# LPEM.net
KiCad netlist of a schematic drawn in EAGLE
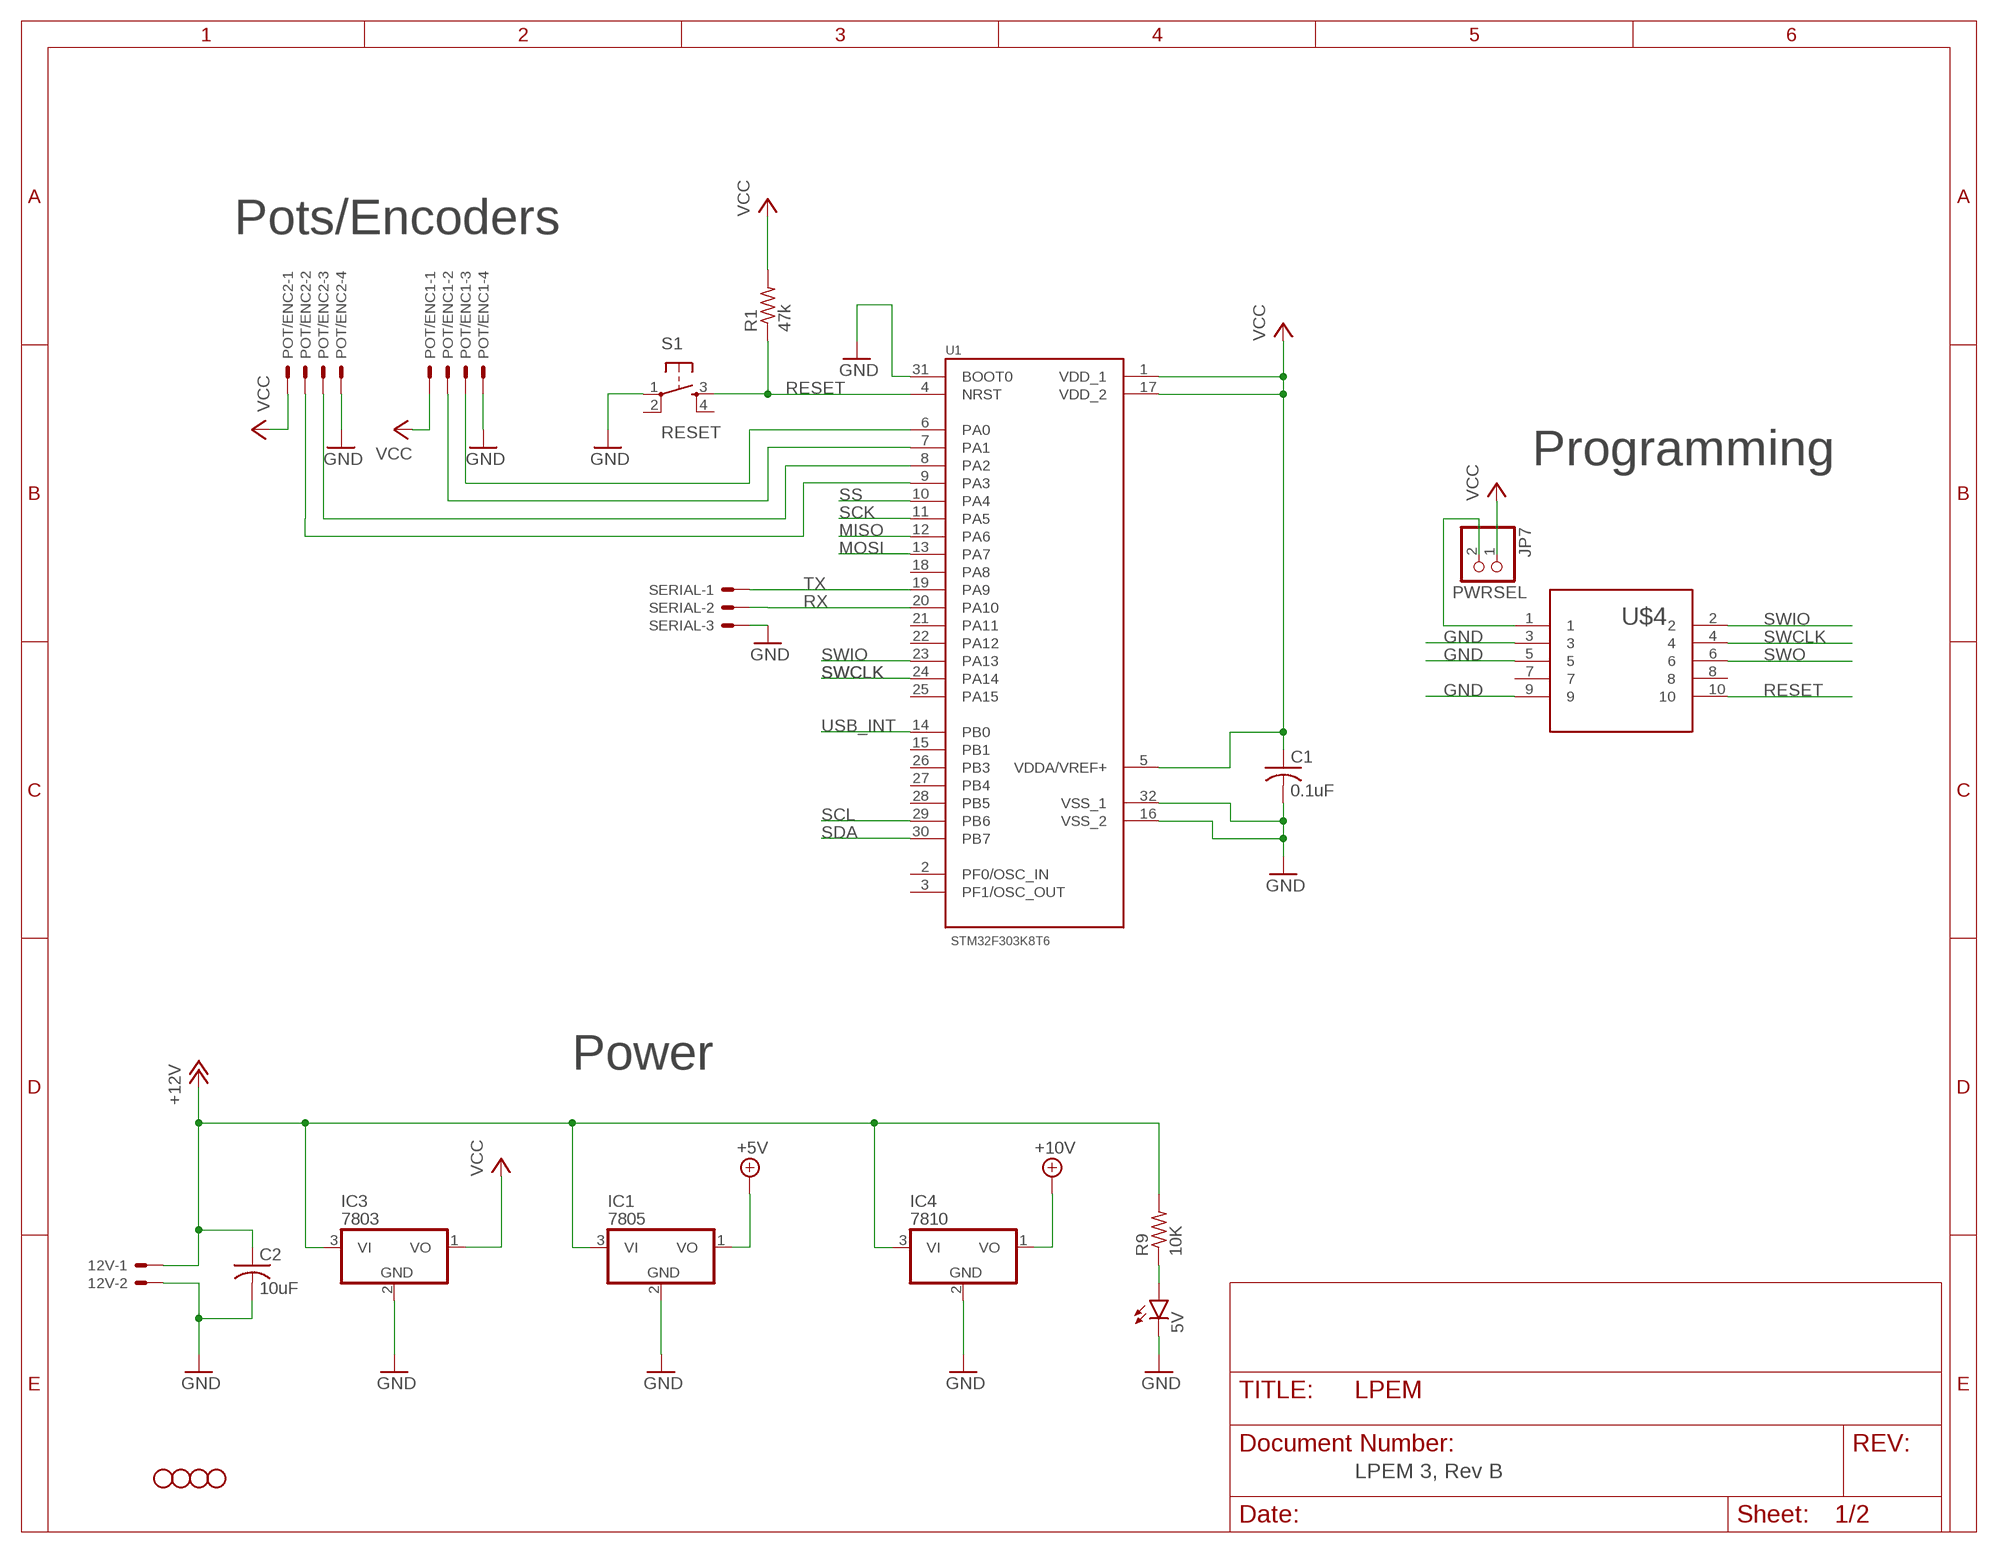
[diagram p0: schematic, sheet 1]
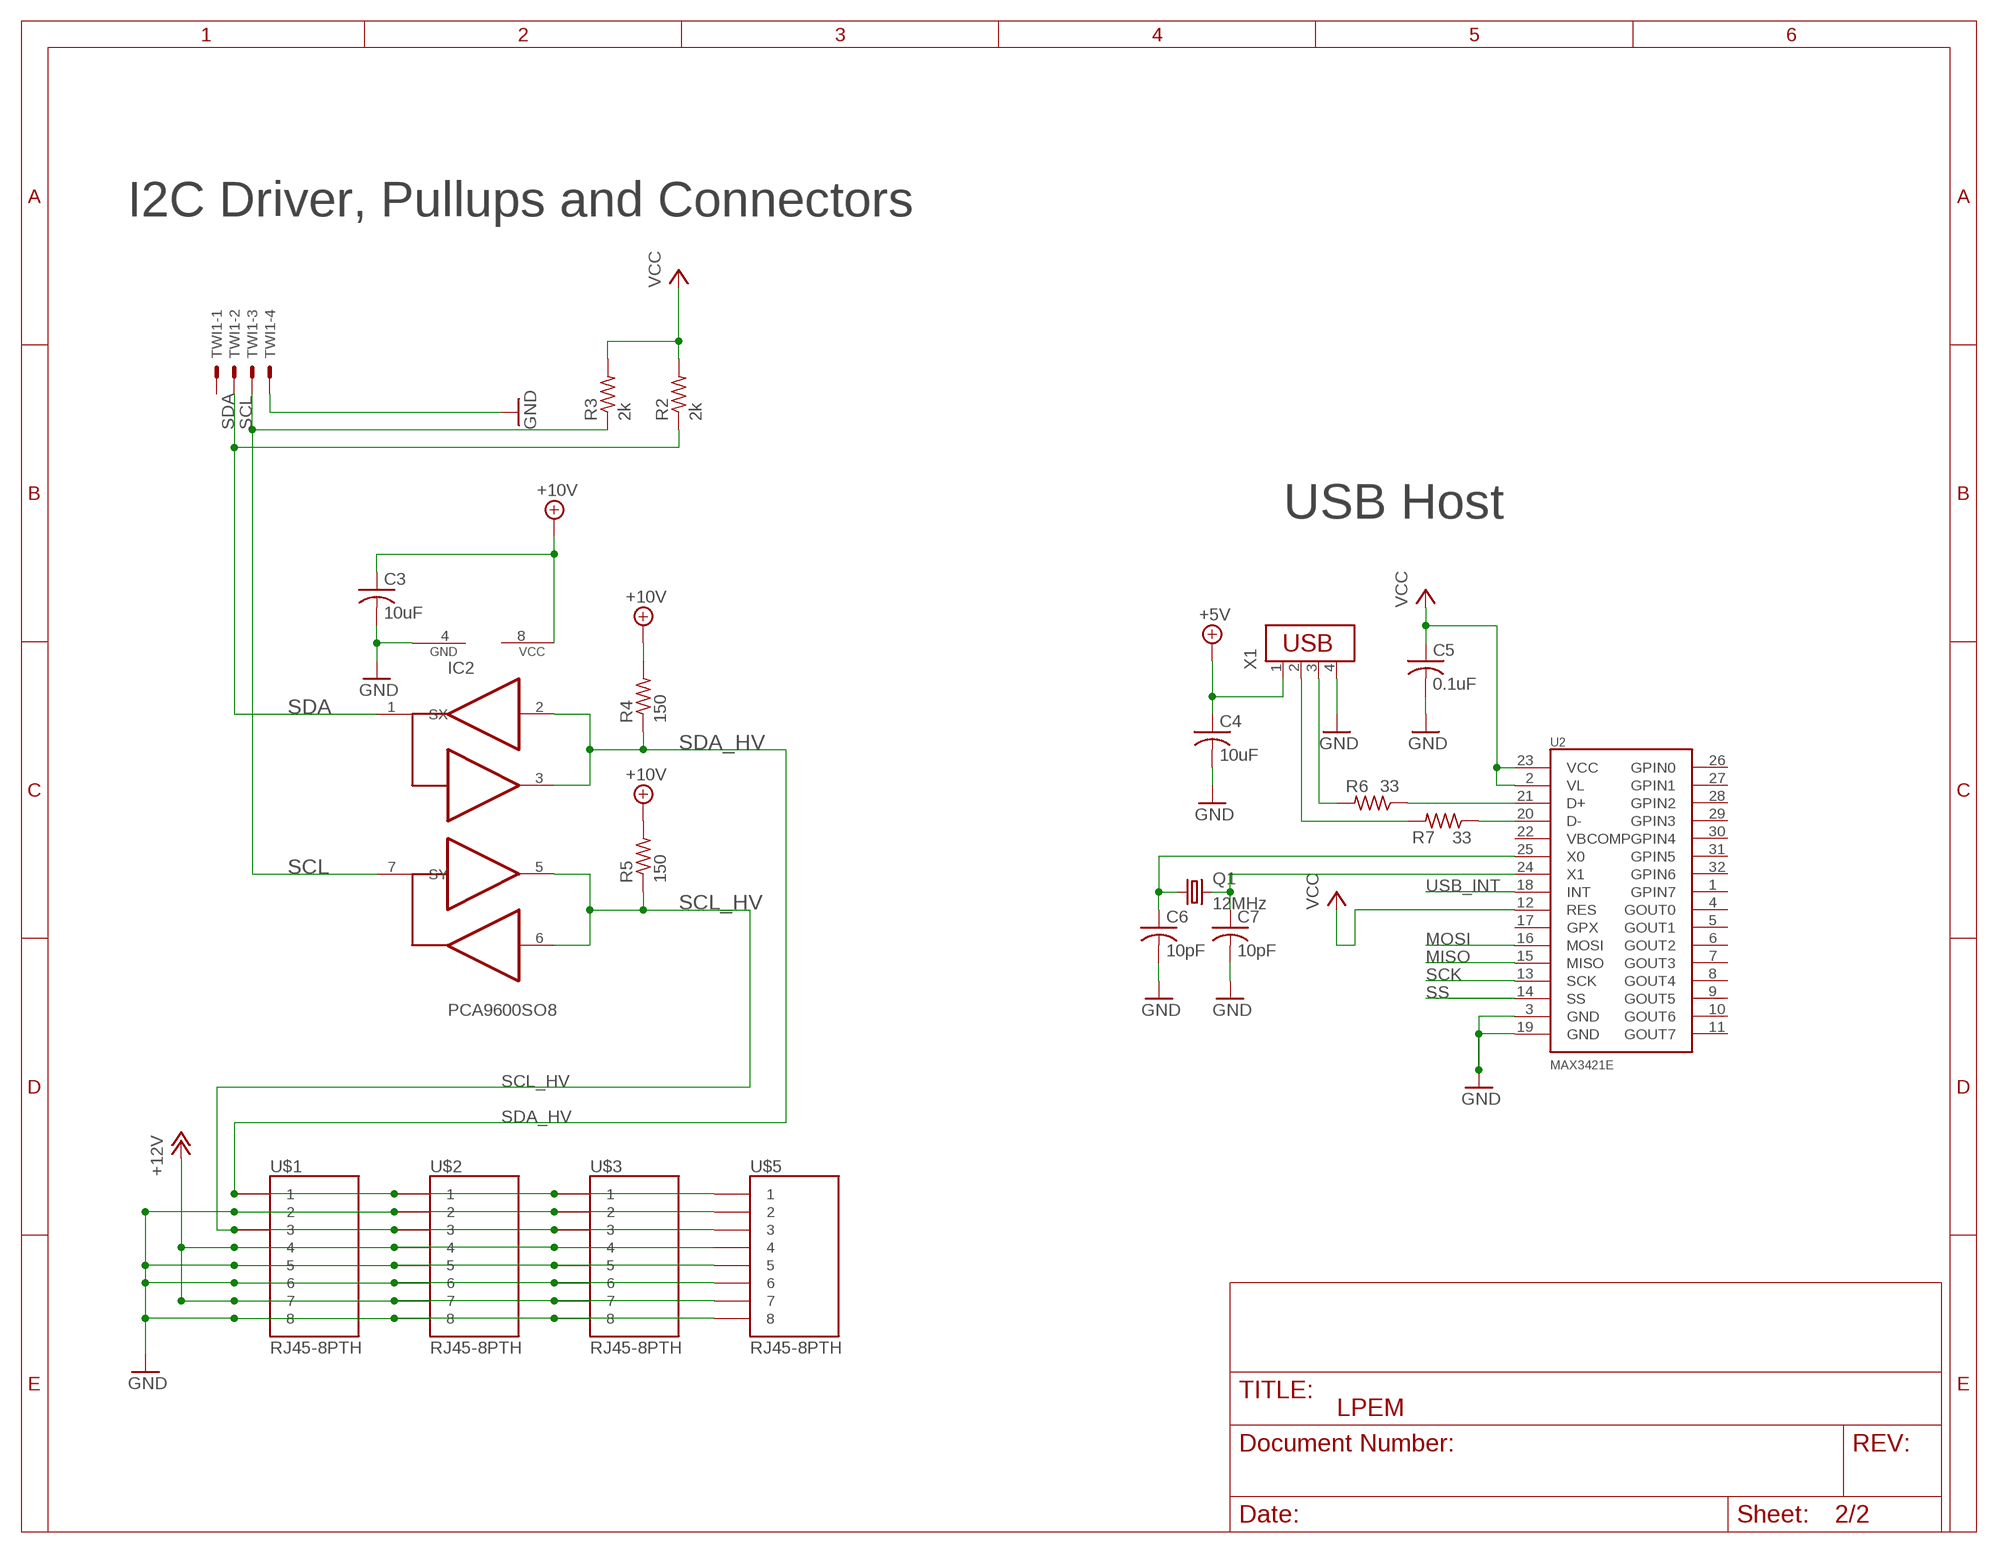
[diagram p1: schematic, sheet 2]

(export (version "E")
  (design (tool "Eeschema 10.0.6"))
  (components
    (comp (ref "C3")
      (value "10uF")
      (footprint "eagle-import:C025-025X050")
      (libsource (lib "eagle-import") (part "C-US025-025X050"))
    )
    (comp (ref "C4")
      (value "10uF")
      (footprint "eagle-import:C025-025X050")
      (libsource (lib "eagle-import") (part "C-US025-025X050"))
    )
    (comp (ref "C5")
      (value "0.1uF")
      (footprint "eagle-import:C025-025X050")
      (libsource (lib "eagle-import") (part "C-US025-025X050"))
    )
    (comp (ref "C6")
      (value "10pF")
      (footprint "eagle-import:C025-025X050")
      (libsource (lib "eagle-import") (part "C-US025-025X050"))
    )
    (comp (ref "C7")
      (value "10pF")
      (footprint "eagle-import:C025-025X050")
      (libsource (lib "eagle-import") (part "C-US025-025X050"))
    )
    (comp (ref "IC2")
      (value "PCA9600SO8")
      (footprint "eagle-import:SO08")
      (libsource (lib "eagle-import") (part "PCA9600SO8"))
    )
    (comp (ref "Q1")
      (value "12MHz")
      (footprint "eagle-import:HC18U-V")
      (libsource (lib "eagle-import") (part "CRYSTALHC18U-V"))
    )
    (comp (ref "R2")
      (value "2k")
      (footprint "eagle-import:0204_5")
      (libsource (lib "eagle-import") (part "R-US_0204/5"))
    )
    (comp (ref "R3")
      (value "2k")
      (footprint "eagle-import:0204_5")
      (libsource (lib "eagle-import") (part "R-US_0204/5"))
    )
    (comp (ref "R4")
      (value "150")
      (footprint "eagle-import:0204_5")
      (libsource (lib "eagle-import") (part "R-US_0204/5"))
    )
    (comp (ref "R5")
      (value "150")
      (footprint "eagle-import:0204_5")
      (libsource (lib "eagle-import") (part "R-US_0204/5"))
    )
    (comp (ref "R6")
      (value "33")
      (footprint "eagle-import:0204_5")
      (libsource (lib "eagle-import") (part "R-US_0204/5"))
    )
    (comp (ref "R7")
      (value "33")
      (footprint "eagle-import:0204_5")
      (libsource (lib "eagle-import") (part "R-US_0204/5"))
    )
    (comp (ref "TWI1")
      (value "22-23-2041")
      (footprint "eagle-import:22-23-2041")
      (fields (field (name "MF") "MOLEX"))
      (libsource (lib "eagle-import") (part "22-23-2041"))
    )
    (comp (ref "U$1")
      (value "RJ45-8PTH")
      (footprint "eagle-import:RJ45-8")
      (libsource (lib "eagle-import") (part "RJ45-8PTH"))
    )
    (comp (ref "U$2")
      (value "RJ45-8PTH")
      (footprint "eagle-import:RJ45-8")
      (libsource (lib "eagle-import") (part "RJ45-8PTH"))
    )
    (comp (ref "U$3")
      (value "RJ45-8PTH")
      (footprint "eagle-import:RJ45-8")
      (libsource (lib "eagle-import") (part "RJ45-8PTH"))
    )
    (comp (ref "U$5")
      (value "RJ45-8PTH")
      (footprint "eagle-import:RJ45-8")
      (libsource (lib "eagle-import") (part "RJ45-8PTH"))
    )
    (comp (ref "U2")
      (value "MAX3421E")
      (footprint "eagle-import:TQFP32-5MM")
      (fields (field (name "MF") "Maxim Integrated"))
      (libsource (lib "eagle-import") (part "MAX3421E"))
    )
    (comp (ref "X1")
      (value "USB-787616")
      (footprint "eagle-import:USB")
      (libsource (lib "eagle-import") (part "USB-787616"))
    )
    (comp (ref "5V")
      (value "LED3MM")
      (footprint "eagle-import:LED3MM")
      (libsource (lib "eagle-import") (part "LED3MM"))
    )
    (comp (ref "12V")
      (value "22-23-2021")
      (footprint "eagle-import:22-23-2021")
      (fields (field (name "MF") "MOLEX"))
      (libsource (lib "eagle-import") (part "22-23-2021"))
    )
    (comp (ref "C1")
      (value "0.1uF")
      (footprint "eagle-import:C025-025X050")
      (libsource (lib "eagle-import") (part "C-US025-025X050"))
    )
    (comp (ref "C2")
      (value "10uF")
      (footprint "eagle-import:C025-025X050")
      (libsource (lib "eagle-import") (part "C-US025-025X050"))
    )
    (comp (ref "IC1")
      (value "7805")
      (footprint "eagle-import:TO92")
      (libsource (lib "eagle-import") (part "78ZL05"))
    )
    (comp (ref "IC3")
      (value "7803")
      (footprint "eagle-import:TO92")
      (libsource (lib "eagle-import") (part "78ZL05"))
    )
    (comp (ref "IC4")
      (value "7810")
      (footprint "eagle-import:TO92")
      (libsource (lib "eagle-import") (part "78ZL05"))
    )
    (comp (ref "JP1")
      (value "STAND-OFF")
      (footprint "eagle-import:STAND-OFF")
      (libsource (lib "eagle-import") (part "STAND-OFF"))
    )
    (comp (ref "JP2")
      (value "STAND-OFF")
      (footprint "eagle-import:STAND-OFF")
      (libsource (lib "eagle-import") (part "STAND-OFF"))
    )
    (comp (ref "JP7")
      (value "PWRSEL")
      (footprint "eagle-import:1X02")
      (libsource (lib "eagle-import") (part "PINHD-1X2"))
    )
    (comp (ref "JP8")
      (value "STAND-OFF")
      (footprint "eagle-import:STAND-OFF")
      (libsource (lib "eagle-import") (part "STAND-OFF"))
    )
    (comp (ref "JP9")
      (value "STAND-OFF")
      (footprint "eagle-import:STAND-OFF")
      (libsource (lib "eagle-import") (part "STAND-OFF"))
    )
    (comp (ref "POT/ENC1")
      (value "22-23-2041")
      (footprint "eagle-import:22-23-2041")
      (fields (field (name "MF") "MOLEX"))
      (libsource (lib "eagle-import") (part "22-23-2041"))
    )
    (comp (ref "POT/ENC2")
      (value "22-23-2041")
      (footprint "eagle-import:22-23-2041")
      (fields (field (name "MF") "MOLEX"))
      (libsource (lib "eagle-import") (part "22-23-2041"))
    )
    (comp (ref "R1")
      (value "47k")
      (footprint "eagle-import:0204_5")
      (libsource (lib "eagle-import") (part "R-US_0204/5"))
    )
    (comp (ref "R9")
      (value "10K")
      (footprint "eagle-import:0204_5")
      (libsource (lib "eagle-import") (part "R-US_0204/5"))
    )
    (comp (ref "S1")
      (value "RESET")
      (footprint "eagle-import:TACTILE-PTH")
      (libsource (lib "eagle-import") (part "TAC_SWITCHPTH"))
    )
    (comp (ref "SERIAL")
      (value "22-23-2031")
      (footprint "eagle-import:22-23-2031")
      (fields (field (name "MF") "MOLEX"))
      (libsource (lib "eagle-import") (part "22-23-2031"))
    )
    (comp (ref "U$4")
      (value "CORTEX_HEADERJ")
      (footprint "eagle-import:CORTEX_HEADER")
      (fields (field (name "MF") "Samtec Inc.") (field (name "MP") "TFM-105-01-S-D-WT"))
      (libsource (lib "eagle-import") (part "CORTEX_HEADERJ"))
    )
    (comp (ref "U1")
      (value "STM32F303K8T6")
      (footprint "eagle-import:QFP80P900X900X160-32N")
      (fields (field (name "MF") "STMicroelectronics"))
      (libsource (lib "eagle-import") (part "STM32F303K8T6"))
    )
  )
  (nets
    (net (code "1") (name "+5V") (class "Default")
      (node (ref "C4") (pin "1") (pinfunction "1_1") (pintype "passive"))
      (node (ref "IC1") (pin "1") (pinfunction "VO_1") (pintype "passive"))
      (node (ref "X1") (pin "1") (pinfunction "1_1") (pintype "passive"))
    )
    (net (code "2") (name "+10V") (class "Default")
      (node (ref "C3") (pin "1") (pinfunction "1_1") (pintype "passive"))
      (node (ref "IC2") (pin "8") (pinfunction "VCC_8") (pintype "power_in"))
      (node (ref "IC4") (pin "1") (pinfunction "VO_1") (pintype "passive"))
      (node (ref "R4") (pin "2") (pinfunction "2_2") (pintype "passive"))
      (node (ref "R5") (pin "2") (pinfunction "2_2") (pintype "passive"))
    )
    (net (code "3") (name "+12V") (class "Default")
      (node (ref "12V") (pin "1") (pinfunction "S_1") (pintype "passive"))
      (node (ref "C2") (pin "1") (pinfunction "1_1") (pintype "passive"))
      (node (ref "IC1") (pin "3") (pinfunction "VI_3") (pintype "input"))
      (node (ref "IC3") (pin "3") (pinfunction "VI_3") (pintype "input"))
      (node (ref "IC4") (pin "3") (pinfunction "VI_3") (pintype "input"))
      (node (ref "R9") (pin "2") (pinfunction "2_2") (pintype "passive"))
      (node (ref "U$1") (pin "4") (pinfunction "4_4") (pintype "bidirectional"))
      (node (ref "U$1") (pin "7") (pinfunction "7_7") (pintype "bidirectional"))
      (node (ref "U$2") (pin "4") (pinfunction "4_4") (pintype "bidirectional"))
      (node (ref "U$2") (pin "7") (pinfunction "7_7") (pintype "bidirectional"))
      (node (ref "U$3") (pin "4") (pinfunction "4_4") (pintype "bidirectional"))
      (node (ref "U$3") (pin "7") (pinfunction "7_7") (pintype "bidirectional"))
      (node (ref "U$5") (pin "4") (pinfunction "4_4") (pintype "bidirectional"))
      (node (ref "U$5") (pin "7") (pinfunction "7_7") (pintype "bidirectional"))
    )
    (net (code "4") (name "GND") (class "Default")
      (node (ref "12V") (pin "2") (pinfunction "S_2") (pintype "passive"))
      (node (ref "5V") (pin "K") (pinfunction "C_K") (pintype "passive"))
      (node (ref "C1") (pin "2") (pinfunction "2_2") (pintype "passive"))
      (node (ref "C2") (pin "2") (pinfunction "2_2") (pintype "passive"))
      (node (ref "C3") (pin "2") (pinfunction "2_2") (pintype "passive"))
      (node (ref "C4") (pin "2") (pinfunction "2_2") (pintype "passive"))
      (node (ref "C5") (pin "2") (pinfunction "2_2") (pintype "passive"))
      (node (ref "C6") (pin "2") (pinfunction "2_2") (pintype "passive"))
      (node (ref "C7") (pin "2") (pinfunction "2_2") (pintype "passive"))
      (node (ref "IC1") (pin "2") (pinfunction "GND_2") (pintype "passive"))
      (node (ref "IC2") (pin "4") (pinfunction "GND_4") (pintype "power_in"))
      (node (ref "IC3") (pin "2") (pinfunction "GND_2") (pintype "passive"))
      (node (ref "IC4") (pin "2") (pinfunction "GND_2") (pintype "passive"))
      (node (ref "POT/ENC1") (pin "4") (pinfunction "S_4") (pintype "passive"))
      (node (ref "POT/ENC2") (pin "4") (pinfunction "S_4") (pintype "passive"))
      (node (ref "S1") (pin "1") (pinfunction "1_1") (pintype "passive"))
      (node (ref "SERIAL") (pin "3") (pinfunction "S_3") (pintype "passive"))
      (node (ref "TWI1") (pin "4") (pinfunction "S_4") (pintype "passive"))
      (node (ref "U$1") (pin "2") (pinfunction "2_2") (pintype "bidirectional"))
      (node (ref "U$1") (pin "5") (pinfunction "5_5") (pintype "bidirectional"))
      (node (ref "U$1") (pin "6") (pinfunction "6_6") (pintype "bidirectional"))
      (node (ref "U$1") (pin "8") (pinfunction "8_8") (pintype "bidirectional"))
      (node (ref "U$2") (pin "2") (pinfunction "2_2") (pintype "bidirectional"))
      (node (ref "U$2") (pin "5") (pinfunction "5_5") (pintype "bidirectional"))
      (node (ref "U$2") (pin "6") (pinfunction "6_6") (pintype "bidirectional"))
      (node (ref "U$2") (pin "8") (pinfunction "8_8") (pintype "bidirectional"))
      (node (ref "U$3") (pin "2") (pinfunction "2_2") (pintype "bidirectional"))
      (node (ref "U$3") (pin "5") (pinfunction "5_5") (pintype "bidirectional"))
      (node (ref "U$3") (pin "6") (pinfunction "6_6") (pintype "bidirectional"))
      (node (ref "U$3") (pin "8") (pinfunction "8_8") (pintype "bidirectional"))
      (node (ref "U$4") (pin "3") (pinfunction "3_3") (pintype "passive"))
      (node (ref "U$4") (pin "5") (pinfunction "5_5") (pintype "passive"))
      (node (ref "U$4") (pin "9") (pinfunction "9_9") (pintype "passive"))
      (node (ref "U$5") (pin "2") (pinfunction "2_2") (pintype "bidirectional"))
      (node (ref "U$5") (pin "5") (pinfunction "5_5") (pintype "bidirectional"))
      (node (ref "U$5") (pin "6") (pinfunction "6_6") (pintype "bidirectional"))
      (node (ref "U$5") (pin "8") (pinfunction "8_8") (pintype "bidirectional"))
      (node (ref "U1") (pin "16") (pinfunction "VSS_2_16") (pintype "power_in"))
      (node (ref "U1") (pin "31") (pinfunction "BOOT0_31") (pintype "input"))
      (node (ref "U1") (pin "32") (pinfunction "VSS_1_32") (pintype "power_in"))
      (node (ref "U2") (pin "19") (pinfunction "GND_19") (pintype "bidirectional"))
      (node (ref "U2") (pin "3") (pinfunction "GND_3") (pintype "bidirectional"))
      (node (ref "X1") (pin "4") (pinfunction "4_4") (pintype "passive"))
    )
    (net (code "5") (name "MISO") (class "Default")
      (node (ref "U1") (pin "12") (pinfunction "PA6_12") (pintype "bidirectional"))
      (node (ref "U2") (pin "15") (pinfunction "MISO_15") (pintype "bidirectional"))
    )
    (net (code "6") (name "MOSI") (class "Default")
      (node (ref "U1") (pin "13") (pinfunction "PA7_13") (pintype "bidirectional"))
      (node (ref "U2") (pin "16") (pinfunction "MOSI_16") (pintype "bidirectional"))
    )
    (net (code "7") (name "Net-(5V-PadA)") (class "Default")
      (node (ref "5V") (pin "A") (pinfunction "A_A") (pintype "passive"))
      (node (ref "R9") (pin "1") (pinfunction "1_1") (pintype "passive"))
    )
    (net (code "8") (name "Net-(JP7-Pad2)") (class "Default")
      (node (ref "JP7") (pin "2") (pinfunction "2_2") (pintype "passive"))
      (node (ref "U$4") (pin "1") (pinfunction "1_1") (pintype "passive"))
    )
    (net (code "9") (name "Net-(POT/ENC1B-S)") (class "Default")
      (node (ref "POT/ENC1") (pin "2") (pinfunction "S_2") (pintype "passive"))
      (node (ref "U1") (pin "7") (pinfunction "PA1_7") (pintype "bidirectional"))
    )
    (net (code "10") (name "Net-(POT/ENC1C-S)") (class "Default")
      (node (ref "POT/ENC1") (pin "3") (pinfunction "S_3") (pintype "passive"))
      (node (ref "U1") (pin "6") (pinfunction "PA0_6") (pintype "bidirectional"))
    )
    (net (code "11") (name "Net-(POT/ENC2B-S)") (class "Default")
      (node (ref "POT/ENC2") (pin "2") (pinfunction "S_2") (pintype "passive"))
      (node (ref "U1") (pin "9") (pinfunction "PA3_9") (pintype "bidirectional"))
    )
    (net (code "12") (name "Net-(POT/ENC2C-S)") (class "Default")
      (node (ref "POT/ENC2") (pin "3") (pinfunction "S_3") (pintype "passive"))
      (node (ref "U1") (pin "8") (pinfunction "PA2_8") (pintype "bidirectional"))
    )
    (net (code "13") (name "Net-(R6-Pad2)") (class "Default")
      (node (ref "R6") (pin "2") (pinfunction "2_2") (pintype "passive"))
      (node (ref "X1") (pin "3") (pinfunction "3_3") (pintype "passive"))
    )
    (net (code "14") (name "Net-(R7-Pad2)") (class "Default")
      (node (ref "R7") (pin "2") (pinfunction "2_2") (pintype "passive"))
      (node (ref "X1") (pin "2") (pinfunction "2_2") (pintype "passive"))
    )
    (net (code "15") (name "Net-(U2-D+)") (class "Default")
      (node (ref "R6") (pin "1") (pinfunction "1_1") (pintype "passive"))
      (node (ref "U2") (pin "21") (pinfunction "D+_21") (pintype "bidirectional"))
    )
    (net (code "16") (name "Net-(U2-D-)") (class "Default")
      (node (ref "R7") (pin "1") (pinfunction "1_1") (pintype "passive"))
      (node (ref "U2") (pin "20") (pinfunction "D-_20") (pintype "bidirectional"))
    )
    (net (code "17") (name "Net-(U2-X0)") (class "Default")
      (node (ref "C6") (pin "1") (pinfunction "1_1") (pintype "passive"))
      (node (ref "Q1") (pin "1") (pinfunction "1_1") (pintype "passive"))
      (node (ref "U2") (pin "25") (pinfunction "X0_25") (pintype "bidirectional"))
    )
    (net (code "18") (name "Net-(U2-X1)") (class "Default")
      (node (ref "C7") (pin "1") (pinfunction "1_1") (pintype "passive"))
      (node (ref "Q1") (pin "2") (pinfunction "2_2") (pintype "passive"))
      (node (ref "U2") (pin "24") (pinfunction "X1_24") (pintype "bidirectional"))
    )
    (net (code "19") (name "RESET") (class "Default")
      (node (ref "R1") (pin "1") (pinfunction "1_1") (pintype "passive"))
      (node (ref "S1") (pin "3") (pinfunction "3_3") (pintype "passive"))
      (node (ref "U$4") (pin "10") (pinfunction "10_10") (pintype "passive"))
      (node (ref "U1") (pin "4") (pinfunction "NRST_4") (pintype "bidirectional"))
    )
    (net (code "20") (name "RX") (class "Default")
      (node (ref "SERIAL") (pin "2") (pinfunction "S_2") (pintype "passive"))
      (node (ref "U1") (pin "20") (pinfunction "PA10_20") (pintype "bidirectional"))
    )
    (net (code "21") (name "SCK") (class "Default")
      (node (ref "U1") (pin "11") (pinfunction "PA5_11") (pintype "bidirectional"))
      (node (ref "U2") (pin "13") (pinfunction "SCK_13") (pintype "bidirectional"))
    )
    (net (code "22") (name "SCL") (class "Default")
      (node (ref "IC2") (pin "7") (pinfunction "SY_7") (pintype "bidirectional"))
      (node (ref "R3") (pin "1") (pinfunction "1_1") (pintype "passive"))
      (node (ref "TWI1") (pin "3") (pinfunction "S_3") (pintype "passive"))
      (node (ref "U1") (pin "29") (pinfunction "PB6_29") (pintype "bidirectional"))
    )
    (net (code "23") (name "SCL_HV") (class "Default")
      (node (ref "IC2") (pin "5") (pinfunction "TY_5") (pintype "output"))
      (node (ref "IC2") (pin "6") (pinfunction "RY_6") (pintype "input"))
      (node (ref "R5") (pin "1") (pinfunction "1_1") (pintype "passive"))
      (node (ref "U$1") (pin "3") (pinfunction "3_3") (pintype "bidirectional"))
      (node (ref "U$2") (pin "3") (pinfunction "3_3") (pintype "bidirectional"))
      (node (ref "U$3") (pin "3") (pinfunction "3_3") (pintype "bidirectional"))
      (node (ref "U$5") (pin "3") (pinfunction "3_3") (pintype "bidirectional"))
    )
    (net (code "24") (name "SDA") (class "Default")
      (node (ref "IC2") (pin "1") (pinfunction "SX_1") (pintype "bidirectional"))
      (node (ref "R2") (pin "1") (pinfunction "1_1") (pintype "passive"))
      (node (ref "TWI1") (pin "2") (pinfunction "S_2") (pintype "passive"))
      (node (ref "U1") (pin "30") (pinfunction "PB7_30") (pintype "bidirectional"))
    )
    (net (code "25") (name "SDA_HV") (class "Default")
      (node (ref "IC2") (pin "2") (pinfunction "RX_2") (pintype "input"))
      (node (ref "IC2") (pin "3") (pinfunction "TX_3") (pintype "output"))
      (node (ref "R4") (pin "1") (pinfunction "1_1") (pintype "passive"))
      (node (ref "U$1") (pin "1") (pinfunction "1_1") (pintype "bidirectional"))
      (node (ref "U$2") (pin "1") (pinfunction "1_1") (pintype "bidirectional"))
      (node (ref "U$3") (pin "1") (pinfunction "1_1") (pintype "bidirectional"))
      (node (ref "U$5") (pin "1") (pinfunction "1_1") (pintype "bidirectional"))
    )
    (net (code "26") (name "SS") (class "Default")
      (node (ref "U1") (pin "10") (pinfunction "PA4_10") (pintype "bidirectional"))
      (node (ref "U2") (pin "14") (pinfunction "SS_14") (pintype "bidirectional"))
    )
    (net (code "27") (name "SWCLK") (class "Default")
      (node (ref "U$4") (pin "4") (pinfunction "4_4") (pintype "passive"))
      (node (ref "U1") (pin "24") (pinfunction "PA14_24") (pintype "bidirectional"))
    )
    (net (code "28") (name "SWIO") (class "Default")
      (node (ref "U$4") (pin "2") (pinfunction "2_2") (pintype "passive"))
      (node (ref "U1") (pin "23") (pinfunction "PA13_23") (pintype "bidirectional"))
    )
    (net (code "29") (name "SWO") (class "Default")
      (node (ref "U$4") (pin "6") (pinfunction "6_6") (pintype "passive"))
    )
    (net (code "30") (name "TX") (class "Default")
      (node (ref "SERIAL") (pin "1") (pinfunction "S_1") (pintype "passive"))
      (node (ref "U1") (pin "19") (pinfunction "PA9_19") (pintype "bidirectional"))
    )
    (net (code "31") (name "USB_INT") (class "Default")
      (node (ref "U1") (pin "14") (pinfunction "PB0_14") (pintype "bidirectional"))
      (node (ref "U2") (pin "18") (pinfunction "INT_18") (pintype "bidirectional"))
    )
    (net (code "32") (name "VCC") (class "Default")
      (node (ref "C1") (pin "1") (pinfunction "1_1") (pintype "passive"))
      (node (ref "C5") (pin "1") (pinfunction "1_1") (pintype "passive"))
      (node (ref "IC3") (pin "1") (pinfunction "VO_1") (pintype "passive"))
      (node (ref "JP7") (pin "1") (pinfunction "1_1") (pintype "passive"))
      (node (ref "POT/ENC1") (pin "1") (pinfunction "S_1") (pintype "passive"))
      (node (ref "POT/ENC2") (pin "1") (pinfunction "S_1") (pintype "passive"))
      (node (ref "R1") (pin "2") (pinfunction "2_2") (pintype "passive"))
      (node (ref "R2") (pin "2") (pinfunction "2_2") (pintype "passive"))
      (node (ref "R3") (pin "2") (pinfunction "2_2") (pintype "passive"))
      (node (ref "U1") (pin "1") (pinfunction "VDD_1_1") (pintype "power_in"))
      (node (ref "U1") (pin "17") (pinfunction "VDD_2_17") (pintype "power_in"))
      (node (ref "U1") (pin "5") (pinfunction "VDDA/VREF+_5") (pintype "power_in"))
      (node (ref "U2") (pin "12") (pinfunction "RES_12") (pintype "bidirectional"))
      (node (ref "U2") (pin "2") (pinfunction "VL_2") (pintype "bidirectional"))
      (node (ref "U2") (pin "23") (pinfunction "VCC_23") (pintype "bidirectional"))
    )
    (net (code "33") (name "unconnected-(S1-Pad2)") (class "Default")
      (node (ref "S1") (pin "2") (pinfunction "2_2") (pintype "passive"))
    )
    (net (code "34") (name "unconnected-(S1-Pad4)") (class "Default")
      (node (ref "S1") (pin "4") (pinfunction "4_4") (pintype "passive"))
    )
    (net (code "35") (name "unconnected-(TWI1A-S-Pad1)") (class "Default")
      (node (ref "TWI1") (pin "1") (pinfunction "S_1") (pintype "passive"))
    )
    (net (code "36") (name "unconnected-(U$4-Pad7)") (class "Default")
      (node (ref "U$4") (pin "7") (pinfunction "7_7") (pintype "passive"))
    )
    (net (code "37") (name "unconnected-(U$4-Pad8)") (class "Default")
      (node (ref "U$4") (pin "8") (pinfunction "8_8") (pintype "passive"))
    )
    (net (code "38") (name "unconnected-(U1-PA8-Pad18)") (class "Default")
      (node (ref "U1") (pin "18") (pinfunction "PA8_18") (pintype "bidirectional"))
    )
    (net (code "39") (name "unconnected-(U1-PA11-Pad21)") (class "Default")
      (node (ref "U1") (pin "21") (pinfunction "PA11_21") (pintype "bidirectional"))
    )
    (net (code "40") (name "unconnected-(U1-PA12-Pad22)") (class "Default")
      (node (ref "U1") (pin "22") (pinfunction "PA12_22") (pintype "bidirectional"))
    )
    (net (code "41") (name "unconnected-(U1-PA15-Pad25)") (class "Default")
      (node (ref "U1") (pin "25") (pinfunction "PA15_25") (pintype "bidirectional"))
    )
    (net (code "42") (name "unconnected-(U1-PB1-Pad15)") (class "Default")
      (node (ref "U1") (pin "15") (pinfunction "PB1_15") (pintype "bidirectional"))
    )
    (net (code "43") (name "unconnected-(U1-PB3-Pad26)") (class "Default")
      (node (ref "U1") (pin "26") (pinfunction "PB3_26") (pintype "bidirectional"))
    )
    (net (code "44") (name "unconnected-(U1-PB4-Pad27)") (class "Default")
      (node (ref "U1") (pin "27") (pinfunction "PB4_27") (pintype "bidirectional"))
    )
    (net (code "45") (name "unconnected-(U1-PB5-Pad28)") (class "Default")
      (node (ref "U1") (pin "28") (pinfunction "PB5_28") (pintype "bidirectional"))
    )
    (net (code "46") (name "unconnected-(U1-PF0{slash}OSC_IN-Pad2)") (class "Default")
      (node (ref "U1") (pin "2") (pinfunction "PF0/OSC_IN_2") (pintype "bidirectional"))
    )
    (net (code "47") (name "unconnected-(U1-PF1{slash}OSC_OUT-Pad3)") (class "Default")
      (node (ref "U1") (pin "3") (pinfunction "PF1/OSC_OUT_3") (pintype "bidirectional"))
    )
    (net (code "48") (name "unconnected-(U2-GOUT0-Pad4)") (class "Default")
      (node (ref "U2") (pin "4") (pinfunction "GOUT0_4") (pintype "bidirectional"))
    )
    (net (code "49") (name "unconnected-(U2-GOUT1-Pad5)") (class "Default")
      (node (ref "U2") (pin "5") (pinfunction "GOUT1_5") (pintype "bidirectional"))
    )
    (net (code "50") (name "unconnected-(U2-GOUT2-Pad6)") (class "Default")
      (node (ref "U2") (pin "6") (pinfunction "GOUT2_6") (pintype "bidirectional"))
    )
    (net (code "51") (name "unconnected-(U2-GOUT3-Pad7)") (class "Default")
      (node (ref "U2") (pin "7") (pinfunction "GOUT3_7") (pintype "bidirectional"))
    )
    (net (code "52") (name "unconnected-(U2-GOUT4-Pad8)") (class "Default")
      (node (ref "U2") (pin "8") (pinfunction "GOUT4_8") (pintype "bidirectional"))
    )
    (net (code "53") (name "unconnected-(U2-GOUT5-Pad9)") (class "Default")
      (node (ref "U2") (pin "9") (pinfunction "GOUT5_9") (pintype "bidirectional"))
    )
    (net (code "54") (name "unconnected-(U2-GOUT6-Pad10)") (class "Default")
      (node (ref "U2") (pin "10") (pinfunction "GOUT6_10") (pintype "bidirectional"))
    )
    (net (code "55") (name "unconnected-(U2-GOUT7-Pad11)") (class "Default")
      (node (ref "U2") (pin "11") (pinfunction "GOUT7_11") (pintype "bidirectional"))
    )
    (net (code "56") (name "unconnected-(U2-GPIN0-Pad26)") (class "Default")
      (node (ref "U2") (pin "26") (pinfunction "GPIN0_26") (pintype "bidirectional"))
    )
    (net (code "57") (name "unconnected-(U2-GPIN1-Pad27)") (class "Default")
      (node (ref "U2") (pin "27") (pinfunction "GPIN1_27") (pintype "bidirectional"))
    )
    (net (code "58") (name "unconnected-(U2-GPIN2-Pad28)") (class "Default")
      (node (ref "U2") (pin "28") (pinfunction "GPIN2_28") (pintype "bidirectional"))
    )
    (net (code "59") (name "unconnected-(U2-GPIN3-Pad29)") (class "Default")
      (node (ref "U2") (pin "29") (pinfunction "GPIN3_29") (pintype "bidirectional"))
    )
    (net (code "60") (name "unconnected-(U2-GPIN4-Pad30)") (class "Default")
      (node (ref "U2") (pin "30") (pinfunction "GPIN4_30") (pintype "bidirectional"))
    )
    (net (code "61") (name "unconnected-(U2-GPIN5-Pad31)") (class "Default")
      (node (ref "U2") (pin "31") (pinfunction "GPIN5_31") (pintype "bidirectional"))
    )
    (net (code "62") (name "unconnected-(U2-GPIN6-Pad32)") (class "Default")
      (node (ref "U2") (pin "32") (pinfunction "GPIN6_32") (pintype "bidirectional"))
    )
    (net (code "63") (name "unconnected-(U2-GPIN7-Pad1)") (class "Default")
      (node (ref "U2") (pin "1") (pinfunction "GPIN7_1") (pintype "bidirectional"))
    )
    (net (code "64") (name "unconnected-(U2-GPX-Pad17)") (class "Default")
      (node (ref "U2") (pin "17") (pinfunction "GPX_17") (pintype "bidirectional"))
    )
    (net (code "65") (name "unconnected-(U2-VBCOMP-Pad22)") (class "Default")
      (node (ref "U2") (pin "22") (pinfunction "VBCOMP_22") (pintype "bidirectional"))
    )
  )
)
